# OSRR-v3.net
KiCad netlist of a schematic drawn in EAGLE
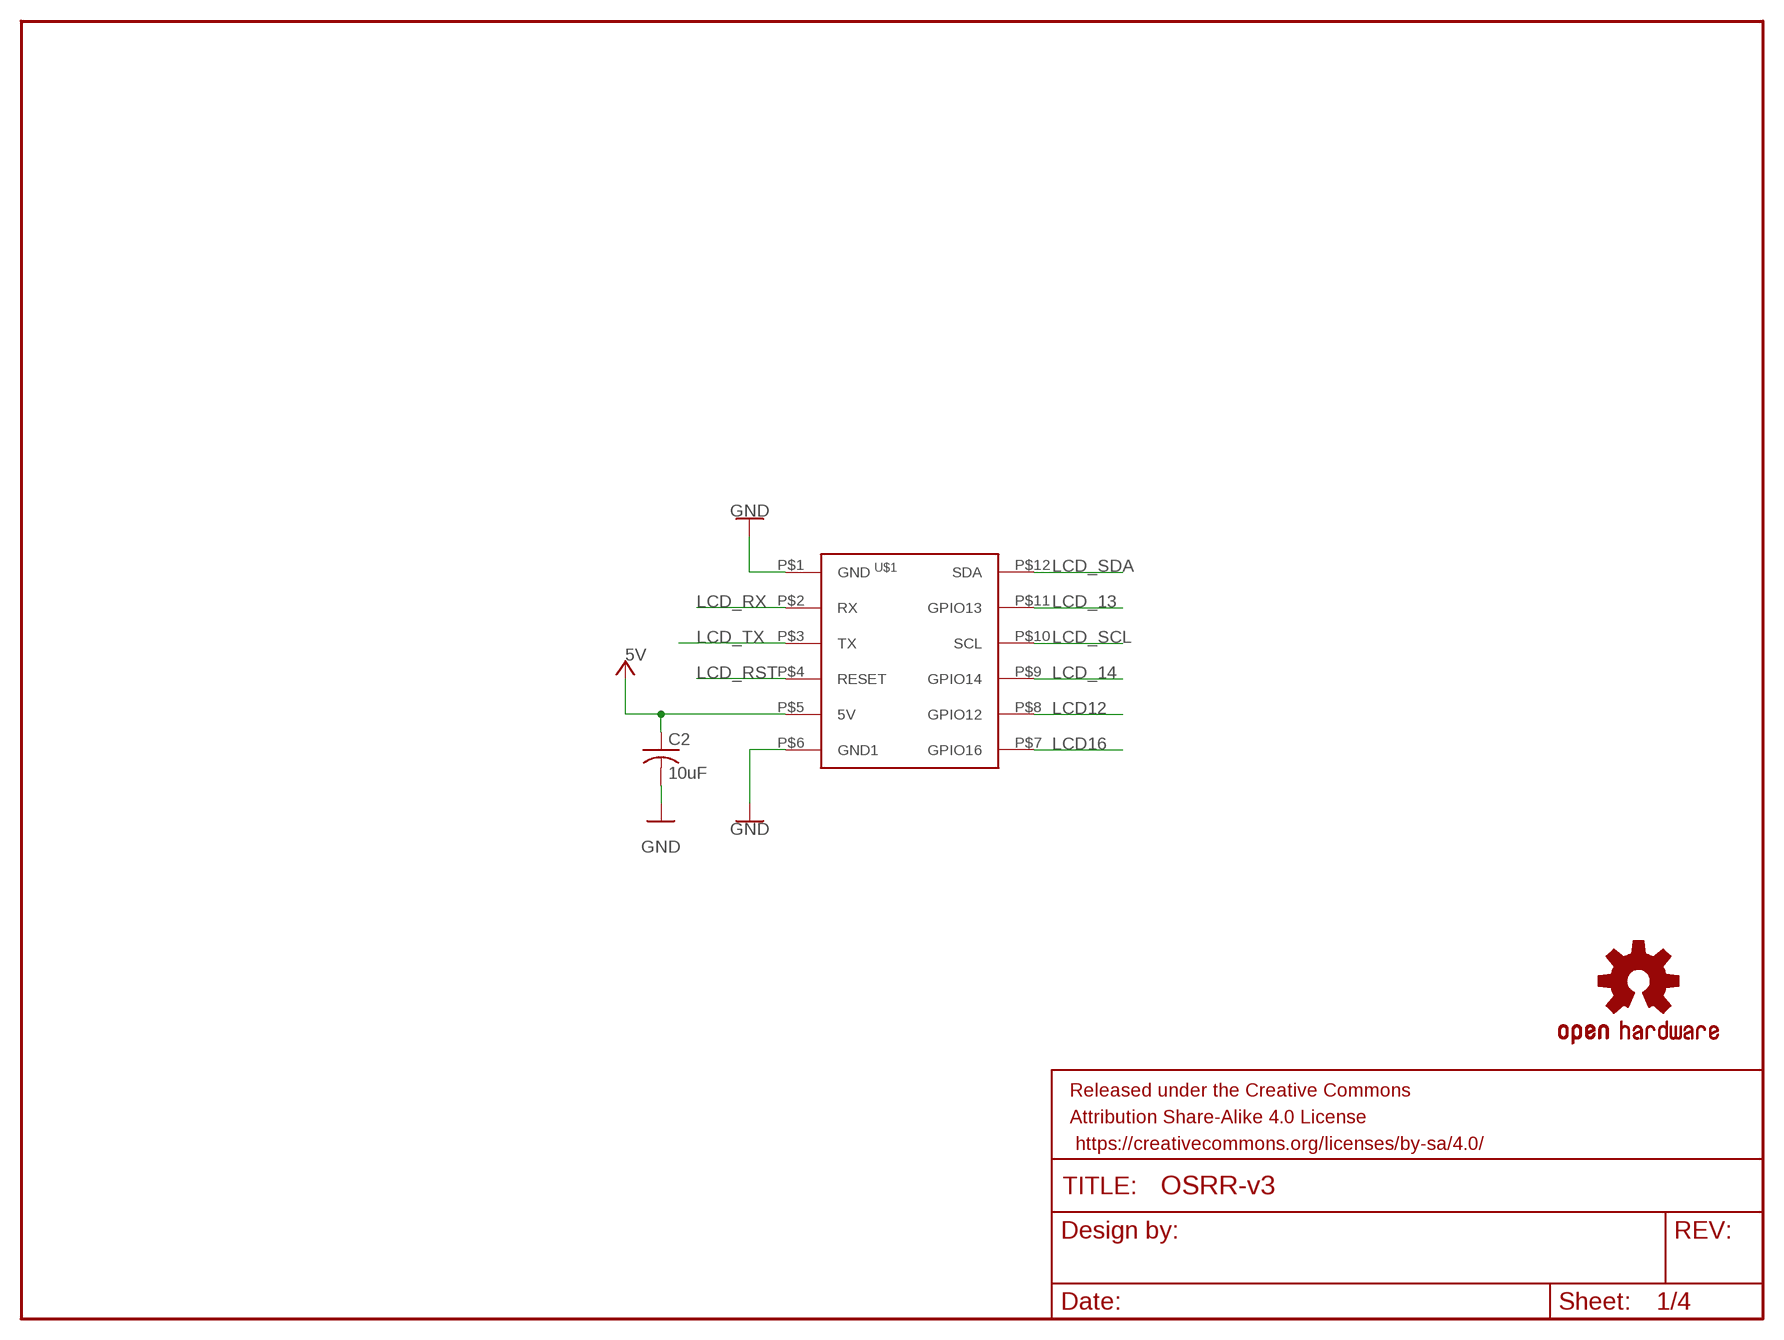
[diagram p0: schematic, sheet 1]
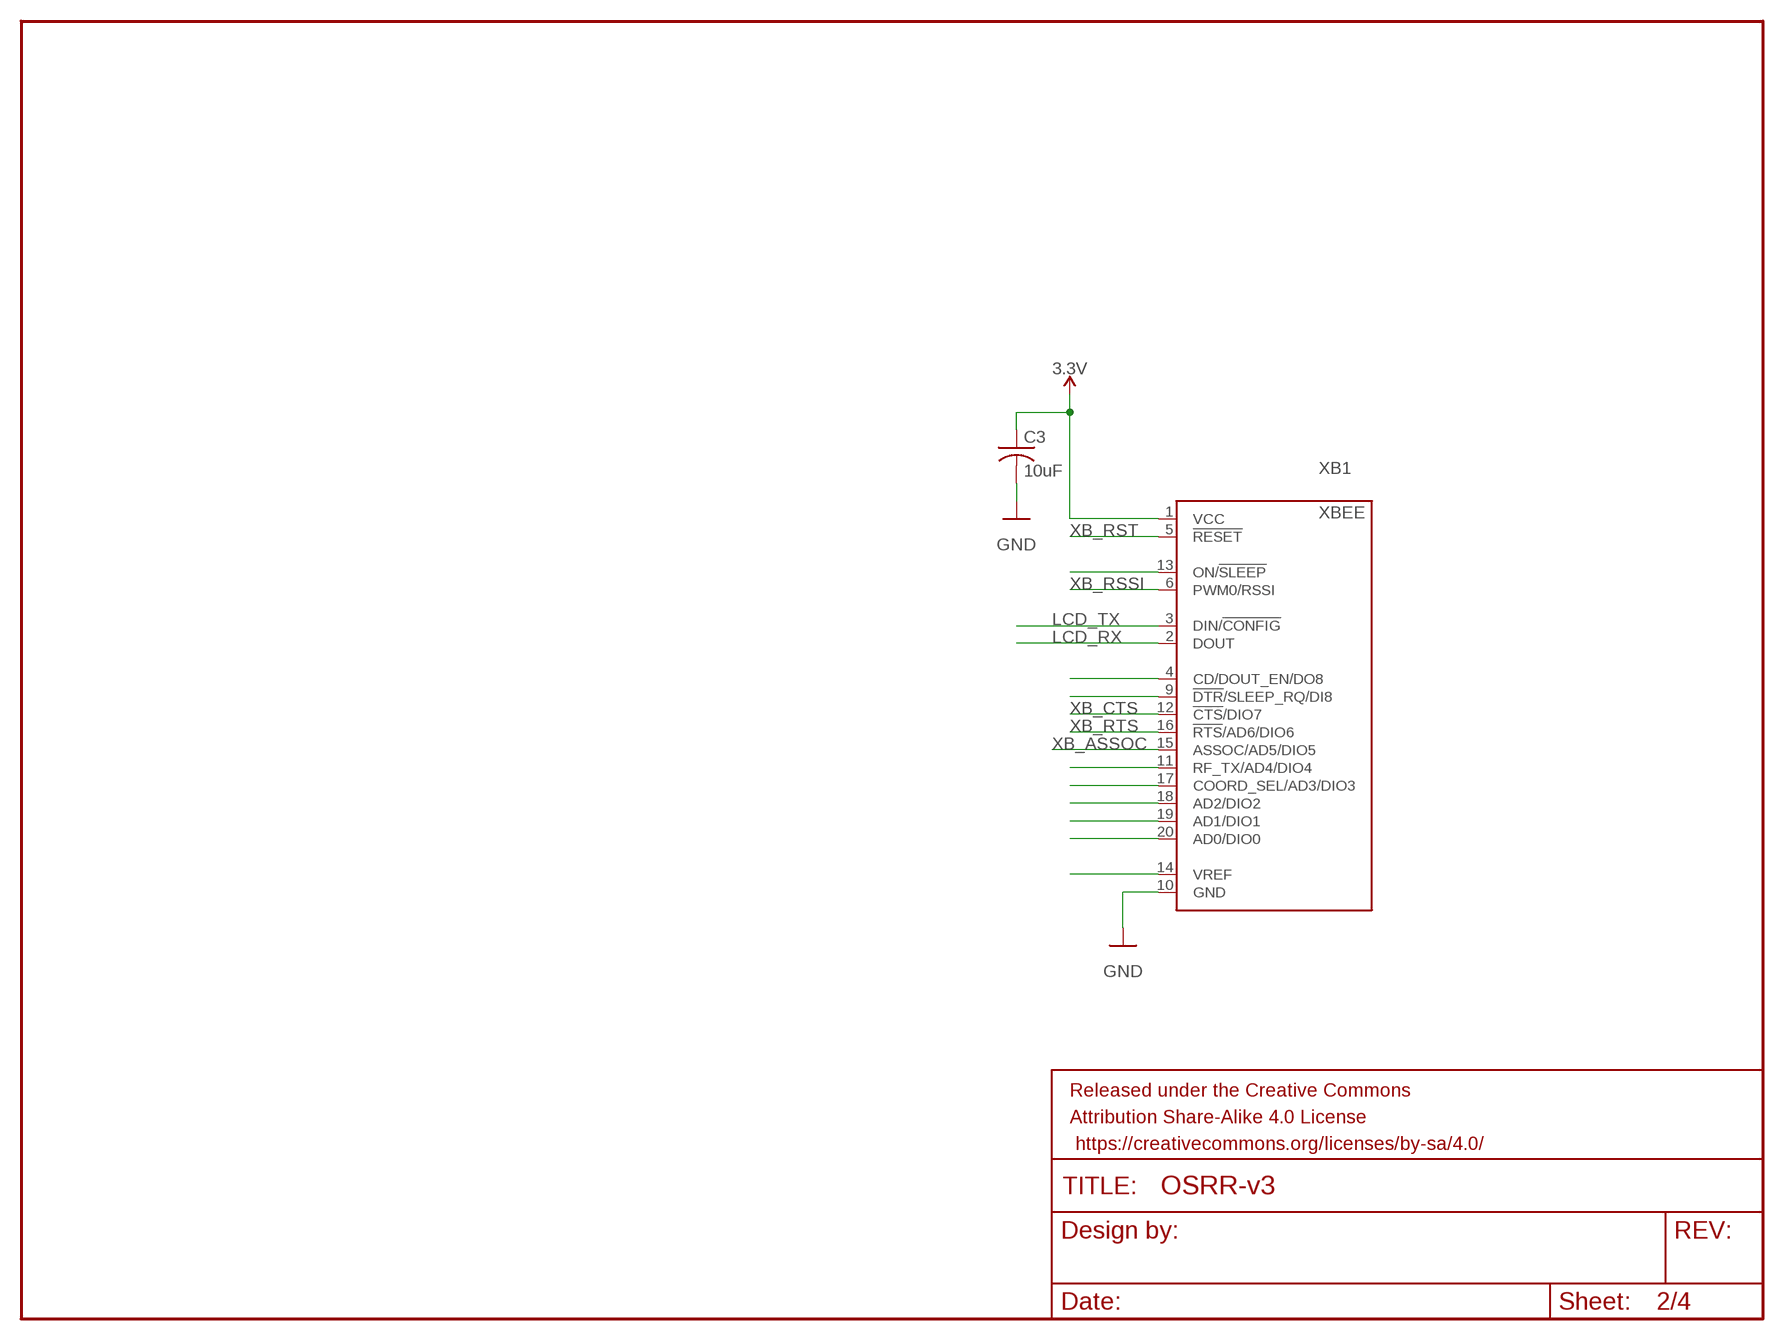
[diagram p1: schematic, sheet 2]
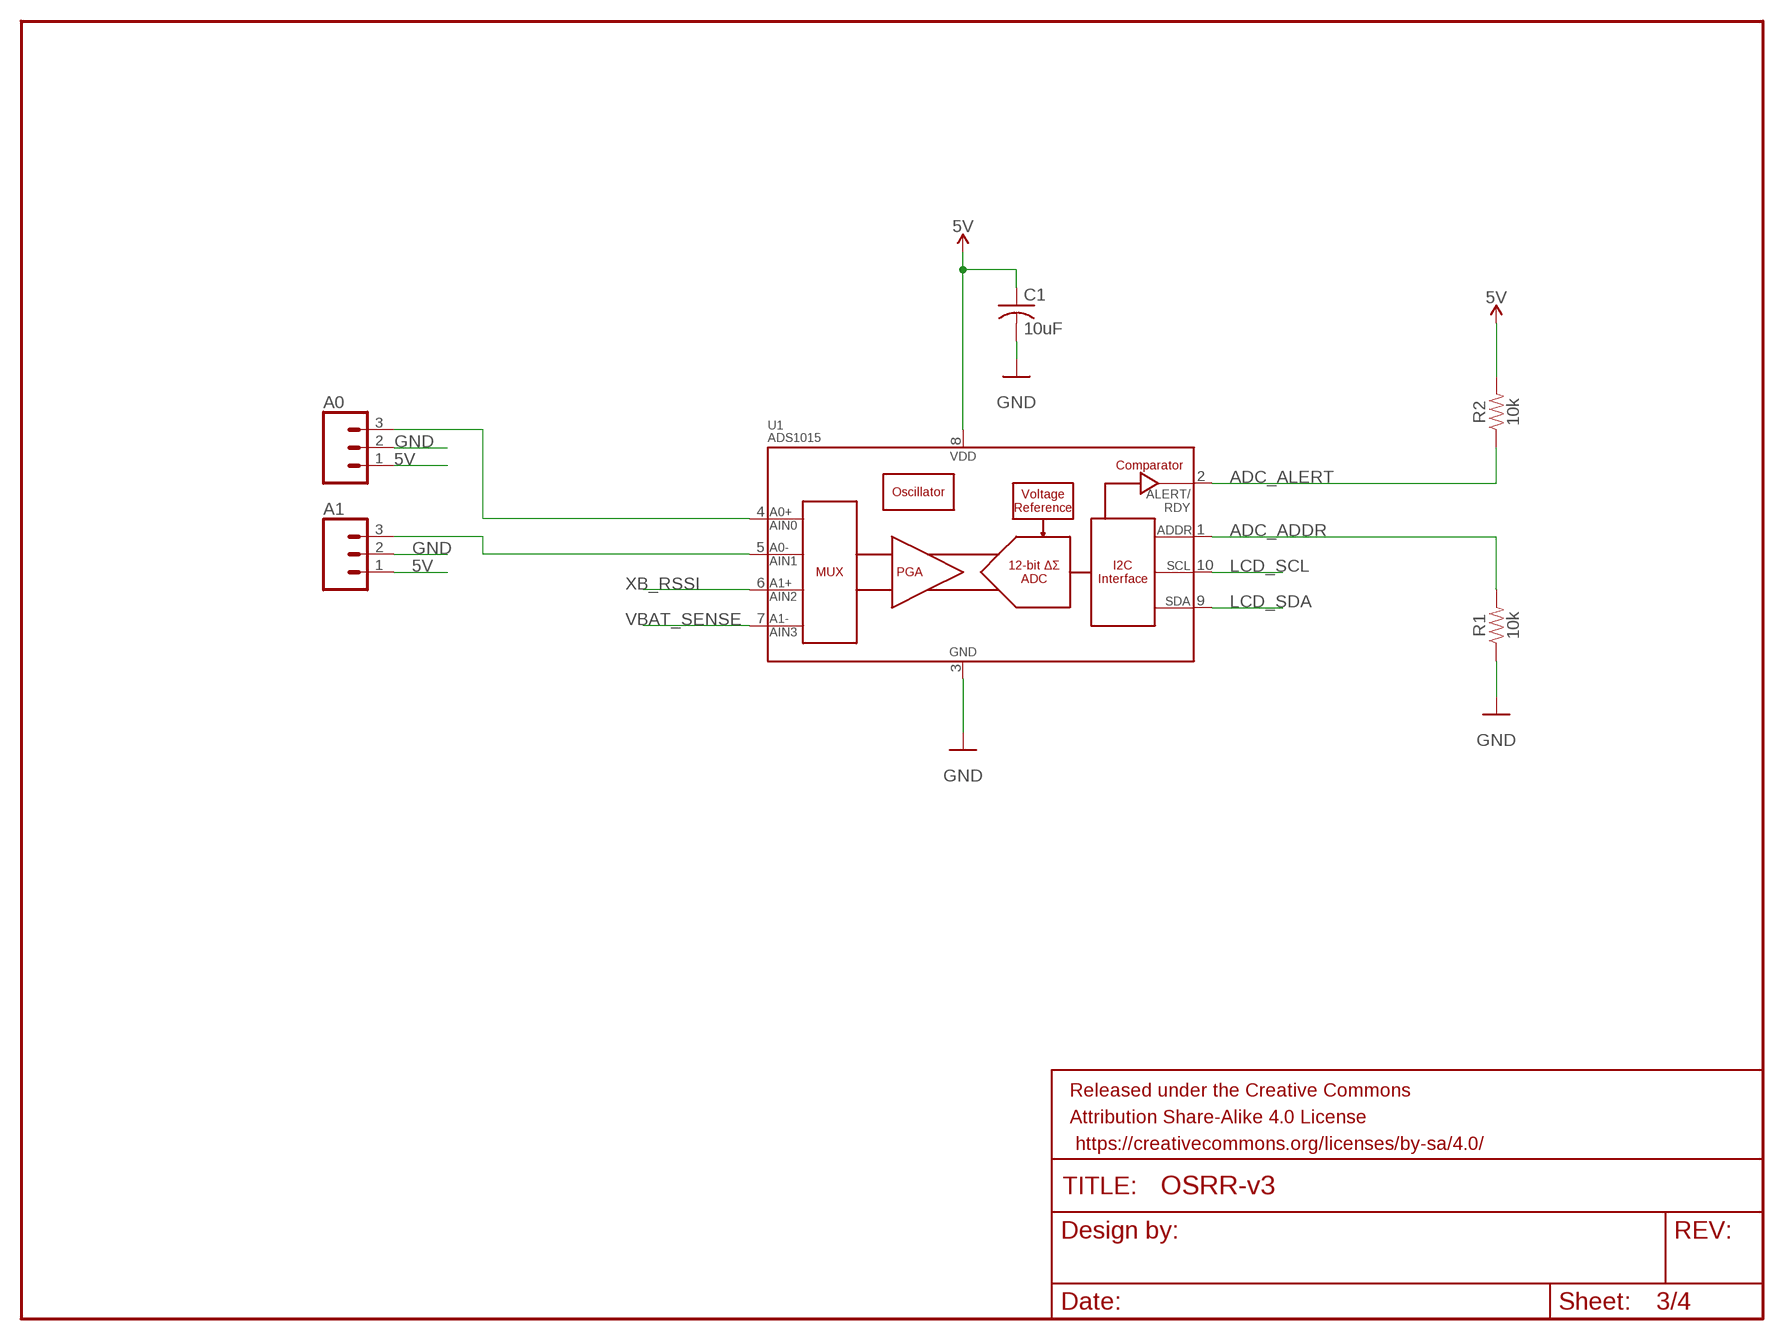
[diagram p2: schematic, sheet 3]
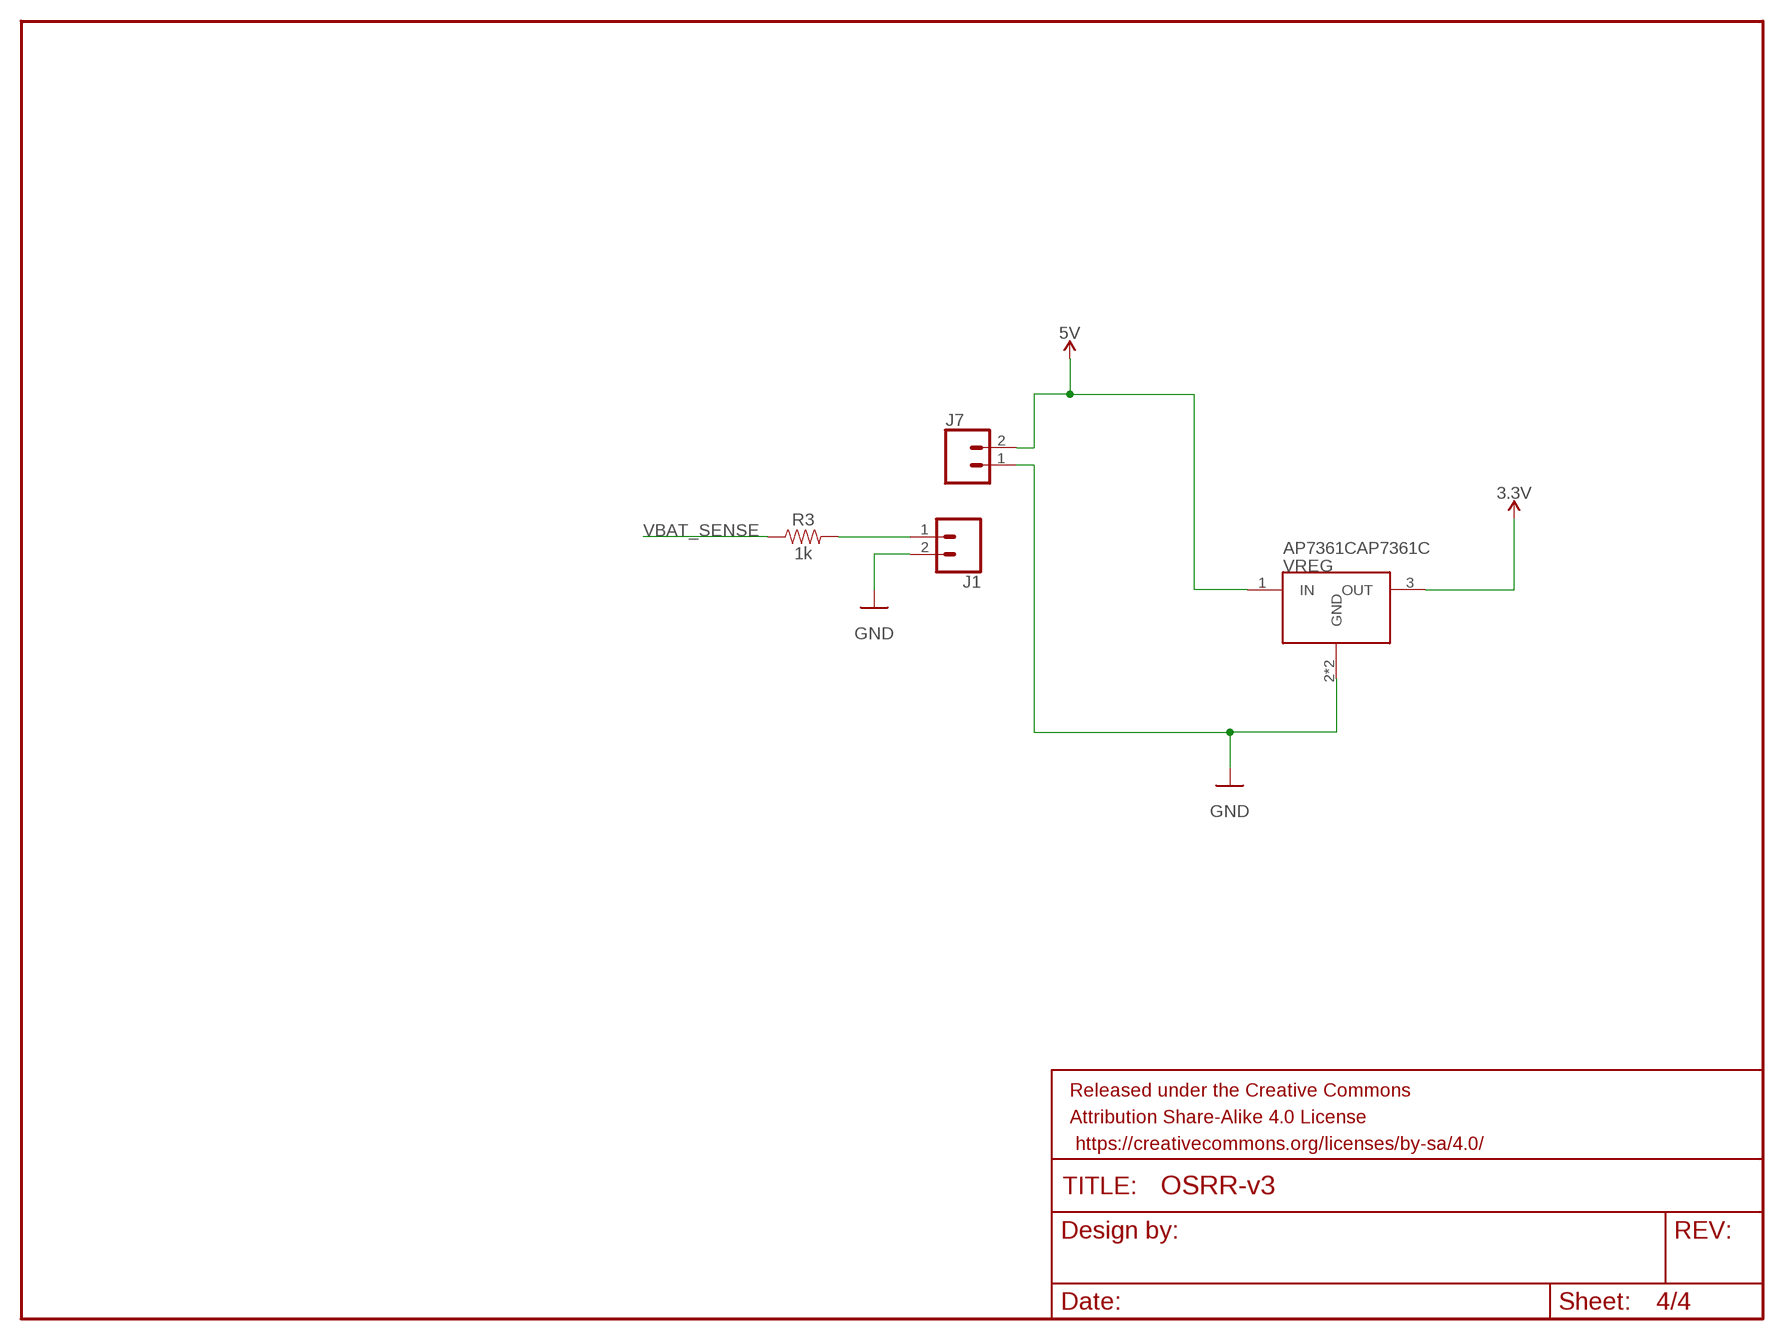
[diagram p3: schematic, sheet 4]

(export (version "E")
  (design (tool "Eeschema 10.0.6"))
  (components
    (comp (ref "C2")
      (value "10uF")
      (footprint "eagle-import:C0603")
      (libsource (lib "eagle-import") (part "C-USC0603"))
    )
    (comp (ref "FRAME1")
      (value "FRAME-LETTER")
      (footprint "eagle-import:CREATIVE_COMMONS")
      (libsource (lib "eagle-import") (part "FRAME-LETTER"))
    )
    (comp (ref "LOGO1")
      (value "OSHW-LOGOS")
      (footprint "eagle-import:OSHW-LOGO-S")
      (libsource (lib "eagle-import") (part "OSHW-LOGOS"))
    )
    (comp (ref "U$1")
      (value "IOD-09")
      (footprint "eagle-import:IOD-9TH")
      (libsource (lib "eagle-import") (part "IOD-09"))
    )
    (comp (ref "C3")
      (value "10uF")
      (footprint "eagle-import:C0603")
      (libsource (lib "eagle-import") (part "C-USC0603"))
    )
    (comp (ref "FRAME2")
      (value "FRAME-LETTER")
      (footprint "eagle-import:CREATIVE_COMMONS")
      (libsource (lib "eagle-import") (part "FRAME-LETTER"))
    )
    (comp (ref "XB1")
      (value "XBEE")
      (footprint "eagle-import:XBEE")
      (fields (field (name "MPN") "XBP24-Z7UIT-004"))
      (libsource (lib "eagle-import") (part "XBEE"))
    )
    (comp (ref "A0")
      (value "CONN_03JST-PTH-VERT")
      (footprint "eagle-import:JST-3-PTH-VERT")
      (libsource (lib "eagle-import") (part "CONN_03JST-PTH-VERT"))
    )
    (comp (ref "A1")
      (value "CONN_03JST-PTH-VERT")
      (footprint "eagle-import:JST-3-PTH-VERT")
      (libsource (lib "eagle-import") (part "CONN_03JST-PTH-VERT"))
    )
    (comp (ref "C1")
      (value "10uF")
      (footprint "eagle-import:C0603")
      (libsource (lib "eagle-import") (part "C-USC0603"))
    )
    (comp (ref "FRAME3")
      (value "FRAME-LETTER")
      (footprint "eagle-import:CREATIVE_COMMONS")
      (libsource (lib "eagle-import") (part "FRAME-LETTER"))
    )
    (comp (ref "R1")
      (value "10k")
      (footprint "eagle-import:0603")
      (libsource (lib "eagle-import") (part "10KOHM-0603-1/10W-1%"))
    )
    (comp (ref "R2")
      (value "10k")
      (footprint "eagle-import:0603")
      (libsource (lib "eagle-import") (part "10KOHM-0603-1/10W-1%"))
    )
    (comp (ref "U1")
      (value "ADS1015")
      (footprint "eagle-import:MSOP10")
      (libsource (lib "eagle-import") (part "ADS1015"))
    )
    (comp (ref "FRAME4")
      (value "FRAME-LETTER")
      (footprint "eagle-import:CREATIVE_COMMONS")
      (libsource (lib "eagle-import") (part "FRAME-LETTER"))
    )
    (comp (ref "J1")
      (value "CONN_02")
      (footprint "eagle-import:1X02")
      (libsource (lib "eagle-import") (part "CONN_02"))
    )
    (comp (ref "J7")
      (value "CONN_02-JST-2-PTH-NO_SILK")
      (footprint "eagle-import:JST-2-PTH-NS")
      (libsource (lib "eagle-import") (part "CONN_02-JST-2-PTH-NO_SILK"))
    )
    (comp (ref "R3")
      (value "1k")
      (footprint "eagle-import:0603")
      (libsource (lib "eagle-import") (part "1KOHM-0603-1/10W-1%"))
    )
    (comp (ref "VREG")
      (value "AP7361CAP7361C")
      (footprint "eagle-import:SOT230P700X180-4")
      (libsource (lib "eagle-import") (part "AP7361CAP7361C"))
    )
  )
  (nets
    (net (code "1") (name "3.3V") (class "Default")
      (node (ref "C3") (pin "1") (pinfunction "1_1") (pintype "passive"))
      (node (ref "VREG") (pin "3") (pinfunction "OUT_3") (pintype "output"))
      (node (ref "XB1") (pin "1") (pinfunction "VCC_1") (pintype "power_in"))
    )
    (net (code "2") (name "5V") (class "Default")
      (node (ref "A0") (pin "1") (pinfunction "1_1") (pintype "passive"))
      (node (ref "A1") (pin "1") (pinfunction "1_1") (pintype "passive"))
      (node (ref "C1") (pin "1") (pinfunction "1_1") (pintype "passive"))
      (node (ref "C2") (pin "1") (pinfunction "1_1") (pintype "passive"))
      (node (ref "J7") (pin "2") (pinfunction "2_2") (pintype "passive"))
      (node (ref "R2") (pin "2") (pinfunction "2_2") (pintype "passive"))
      (node (ref "U$1") (pin "P$5") (pinfunction "5V_P$5") (pintype "bidirectional"))
      (node (ref "U1") (pin "8") (pinfunction "VDD_8") (pintype "bidirectional"))
      (node (ref "VREG") (pin "1") (pinfunction "IN_1") (pintype "input"))
    )
    (net (code "3") (name "ADC_ADDR") (class "Default")
      (node (ref "R1") (pin "2") (pinfunction "2_2") (pintype "passive"))
      (node (ref "U1") (pin "1") (pinfunction "ADDR_1") (pintype "bidirectional"))
    )
    (net (code "4") (name "ADC_ALERT") (class "Default")
      (node (ref "R2") (pin "1") (pinfunction "1_1") (pintype "passive"))
      (node (ref "U1") (pin "2") (pinfunction "ALERT/RDY_2") (pintype "bidirectional"))
    )
    (net (code "5") (name "GND") (class "Default")
      (node (ref "A0") (pin "2") (pinfunction "2_2") (pintype "passive"))
      (node (ref "A1") (pin "2") (pinfunction "2_2") (pintype "passive"))
      (node (ref "C1") (pin "2") (pinfunction "2_2") (pintype "passive"))
      (node (ref "C2") (pin "2") (pinfunction "2_2") (pintype "passive"))
      (node (ref "C3") (pin "2") (pinfunction "2_2") (pintype "passive"))
      (node (ref "J1") (pin "2") (pinfunction "2_2") (pintype "passive"))
      (node (ref "J7") (pin "1") (pinfunction "1_1") (pintype "passive"))
      (node (ref "R1") (pin "1") (pinfunction "1_1") (pintype "passive"))
      (node (ref "U$1") (pin "P$1") (pinfunction "GND_P$1") (pintype "bidirectional"))
      (node (ref "U$1") (pin "P$6") (pinfunction "GND1_P$6") (pintype "bidirectional"))
      (node (ref "U1") (pin "3") (pinfunction "VSS_3") (pintype "bidirectional"))
      (node (ref "VREG") (pin "2") (pinfunction "GND_2") (pintype "power_in"))
      (node (ref "VREG") (pin "4") (pinfunction "GND_4") (pintype "power_in"))
      (node (ref "XB1") (pin "10") (pinfunction "GND_10") (pintype "power_in"))
    )
    (net (code "6") (name "LCD12") (class "Default")
      (node (ref "U$1") (pin "P$8") (pinfunction "GPIO12_P$8") (pintype "bidirectional"))
    )
    (net (code "7") (name "LCD16") (class "Default")
      (node (ref "U$1") (pin "P$7") (pinfunction "GPIO16_P$7") (pintype "bidirectional"))
    )
    (net (code "8") (name "LCD_13") (class "Default")
      (node (ref "U$1") (pin "P$11") (pinfunction "GPIO13_P$11") (pintype "bidirectional"))
    )
    (net (code "9") (name "LCD_14") (class "Default")
      (node (ref "U$1") (pin "P$9") (pinfunction "GPIO14_P$9") (pintype "bidirectional"))
    )
    (net (code "10") (name "LCD_RST") (class "Default")
      (node (ref "U$1") (pin "P$4") (pinfunction "RESET_P$4") (pintype "bidirectional"))
    )
    (net (code "11") (name "LCD_RX") (class "Default")
      (node (ref "U$1") (pin "P$2") (pinfunction "RX_P$2") (pintype "bidirectional"))
      (node (ref "XB1") (pin "2") (pinfunction "DOUT_2") (pintype "output"))
    )
    (net (code "12") (name "LCD_SCL") (class "Default")
      (node (ref "U$1") (pin "P$10") (pinfunction "SCL_P$10") (pintype "bidirectional"))
      (node (ref "U1") (pin "10") (pinfunction "SCL_10") (pintype "bidirectional"))
    )
    (net (code "13") (name "LCD_SDA") (class "Default")
      (node (ref "U$1") (pin "P$12") (pinfunction "SDA_P$12") (pintype "bidirectional"))
      (node (ref "U1") (pin "9") (pinfunction "SDA_9") (pintype "bidirectional"))
    )
    (net (code "14") (name "LCD_TX") (class "Default")
      (node (ref "U$1") (pin "P$3") (pinfunction "TX_P$3") (pintype "bidirectional"))
      (node (ref "XB1") (pin "3") (pinfunction "DIN/~{CONFIG}_3") (pintype "input"))
    )
    (net (code "15") (name "Net-(J1-Pad1)") (class "Default")
      (node (ref "J1") (pin "1") (pinfunction "1_1") (pintype "passive"))
      (node (ref "R3") (pin "2") (pinfunction "2_2") (pintype "passive"))
    )
    (net (code "16") (name "Net-(U1-AIN0)") (class "Default")
      (node (ref "A0") (pin "3") (pinfunction "3_3") (pintype "passive"))
      (node (ref "U1") (pin "4") (pinfunction "AIN0_4") (pintype "bidirectional"))
    )
    (net (code "17") (name "Net-(U1-AIN1)") (class "Default")
      (node (ref "A1") (pin "3") (pinfunction "3_3") (pintype "passive"))
      (node (ref "U1") (pin "5") (pinfunction "AIN1_5") (pintype "bidirectional"))
    )
    (net (code "18") (name "VBAT_SENSE") (class "Default")
      (node (ref "R3") (pin "1") (pinfunction "1_1") (pintype "passive"))
      (node (ref "U1") (pin "7") (pinfunction "AIN3_7") (pintype "bidirectional"))
    )
    (net (code "19") (name "XB_ASSOC") (class "Default")
      (node (ref "XB1") (pin "15") (pinfunction "ASSOC/AD5/DIO5_15") (pintype "bidirectional"))
    )
    (net (code "20") (name "XB_CTS") (class "Default")
      (node (ref "XB1") (pin "12") (pinfunction "~{CTS}/DIO7_12") (pintype "bidirectional"))
    )
    (net (code "21") (name "XB_RSSI") (class "Default")
      (node (ref "U1") (pin "6") (pinfunction "AIN2_6") (pintype "bidirectional"))
      (node (ref "XB1") (pin "6") (pinfunction "PWM0/RSSI_6") (pintype "output"))
    )
    (net (code "22") (name "XB_RST") (class "Default")
      (node (ref "XB1") (pin "5") (pinfunction "~{RESET}_5") (pintype "input"))
    )
    (net (code "23") (name "XB_RTS") (class "Default")
      (node (ref "XB1") (pin "16") (pinfunction "~{RTS}/AD6/DIO6_16") (pintype "bidirectional"))
    )
    (net (code "24") (name "unconnected-(XB1-AD0{slash}DIO0-Pad20)") (class "Default")
      (node (ref "XB1") (pin "20") (pinfunction "AD0/DIO0_20") (pintype "bidirectional"))
    )
    (net (code "25") (name "unconnected-(XB1-AD1{slash}DIO1-Pad19)") (class "Default")
      (node (ref "XB1") (pin "19") (pinfunction "AD1/DIO1_19") (pintype "bidirectional"))
    )
    (net (code "26") (name "unconnected-(XB1-AD2{slash}DIO2-Pad18)") (class "Default")
      (node (ref "XB1") (pin "18") (pinfunction "AD2/DIO2_18") (pintype "bidirectional"))
    )
    (net (code "27") (name "unconnected-(XB1-CD{slash}DOUT_EN{slash}DO8-Pad4)") (class "Default")
      (node (ref "XB1") (pin "4") (pinfunction "CD/DOUT_EN/DO8_4") (pintype "output"))
    )
    (net (code "28") (name "unconnected-(XB1-COORD_SEL{slash}AD3{slash}DIO3-Pad17)") (class "Default")
      (node (ref "XB1") (pin "17") (pinfunction "COORD_SEL/AD3/DIO3_17") (pintype "bidirectional"))
    )
    (net (code "29") (name "unconnected-(XB1-ON{slash}~{SLEEP}-Pad13)") (class "Default")
      (node (ref "XB1") (pin "13") (pinfunction "ON/~{SLEEP}_13") (pintype "output"))
    )
    (net (code "30") (name "unconnected-(XB1-RF_TX{slash}AD4{slash}DIO4-Pad11)") (class "Default")
      (node (ref "XB1") (pin "11") (pinfunction "RF_TX/AD4/DIO4_11") (pintype "bidirectional"))
    )
    (net (code "31") (name "unconnected-(XB1-VREF-Pad14)") (class "Default")
      (node (ref "XB1") (pin "14") (pinfunction "VREF_14") (pintype "input"))
    )
    (net (code "32") (name "unconnected-(XB1-~{DTR}{slash}SLEEP_RQ{slash}DI8-Pad9)") (class "Default")
      (node (ref "XB1") (pin "9") (pinfunction "~{DTR}/SLEEP_RQ/DI8_9") (pintype "bidirectional"))
    )
  )
)
